# S107S1A.net
KiCad netlist of a schematic drawn in EAGLE
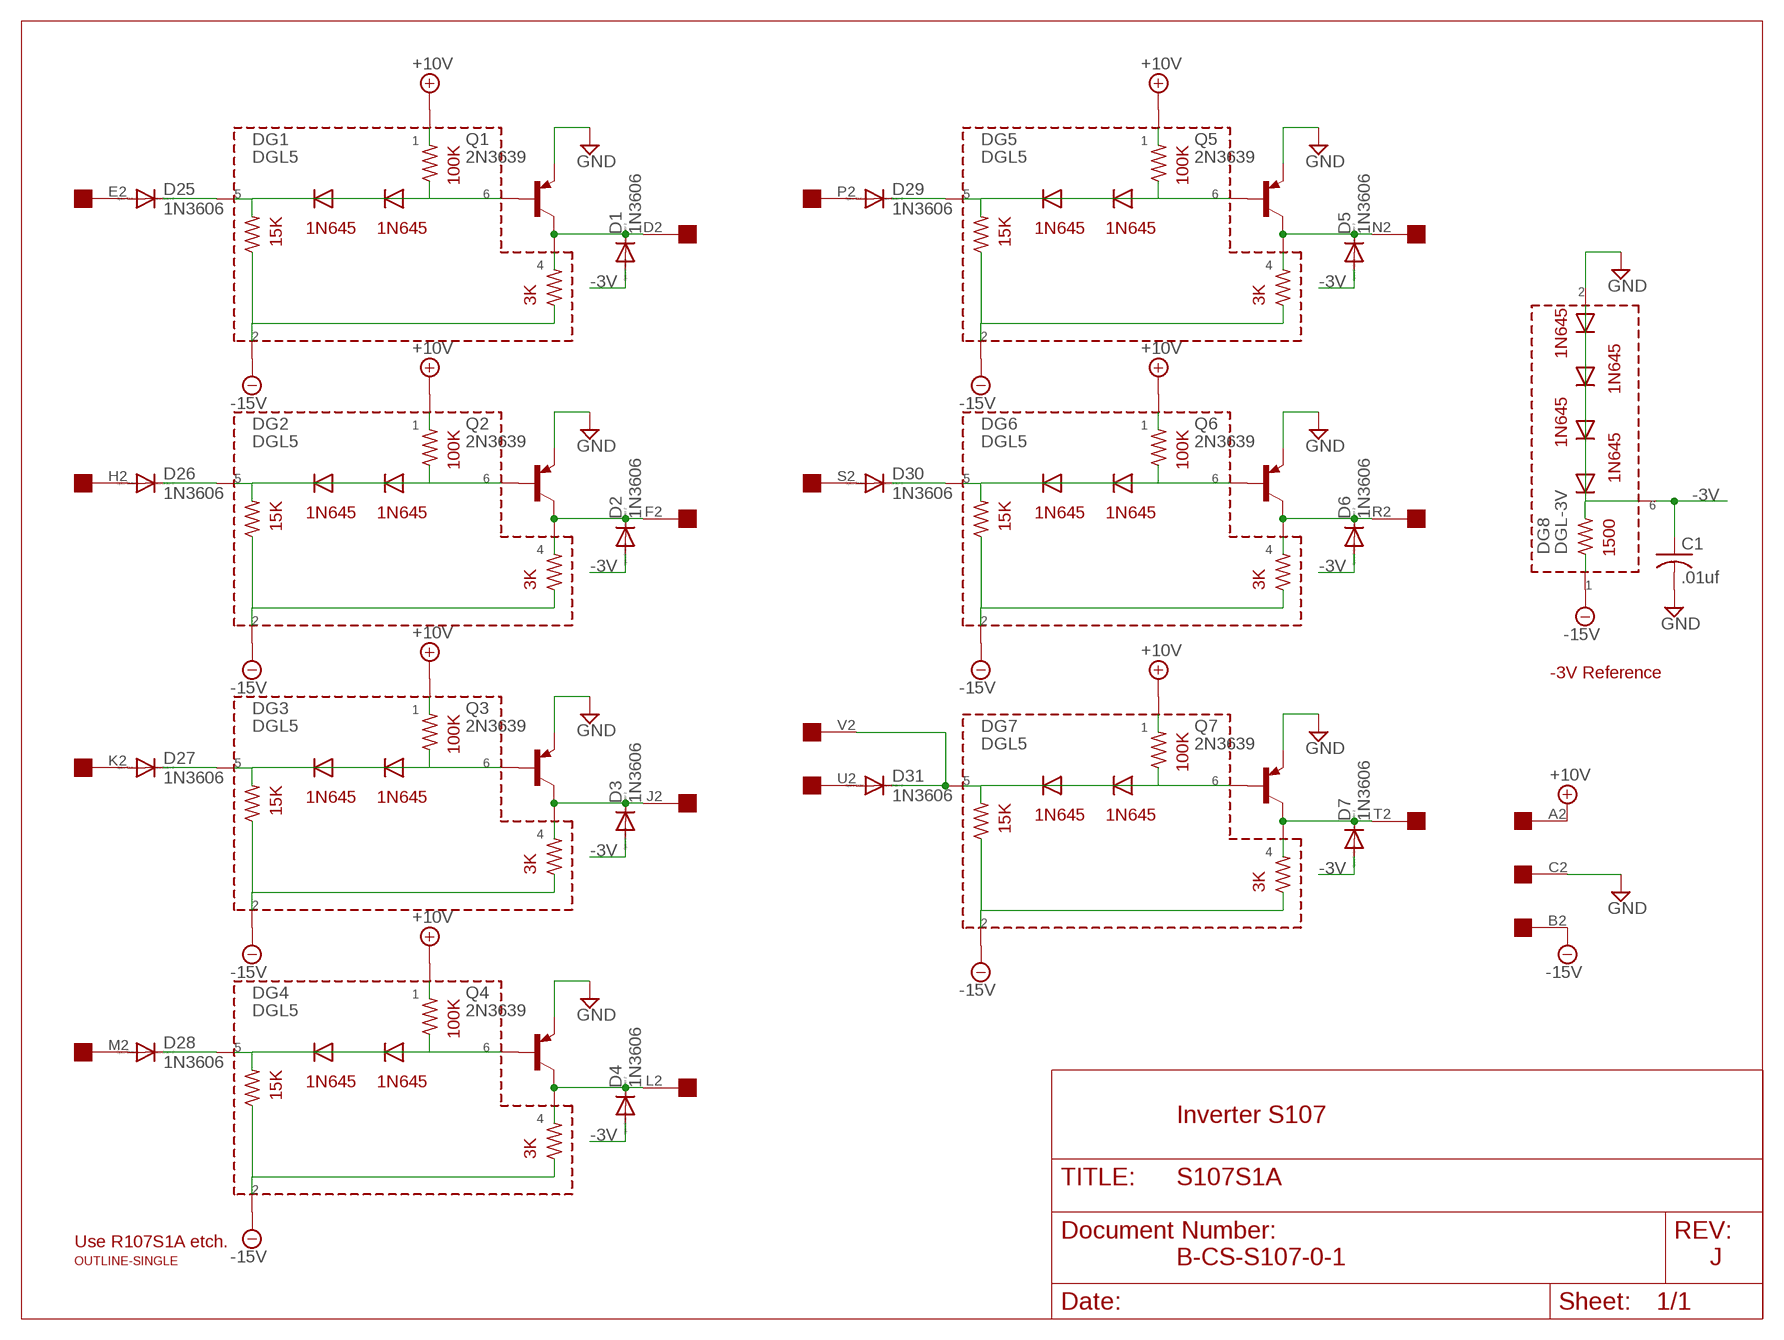
[diagram p0: schematic, sheet 1]

(export (version "E")
  (design (tool "Eeschema 10.0.6"))
  (components
    (comp (ref "C1")
      (value ".01uf")
      (footprint "eagle-import:C050-025X075")
      (libsource (lib "eagle-import") (part "C-US050-025X075"))
    )
    (comp (ref "D1")
      (value "1N3606")
      (footprint "eagle-import:DO35-10")
      (libsource (lib "eagle-import") (part "1N4148DO35-10"))
    )
    (comp (ref "D2")
      (value "1N3606")
      (footprint "eagle-import:DO35-10")
      (libsource (lib "eagle-import") (part "1N4148DO35-10"))
    )
    (comp (ref "D3")
      (value "1N3606")
      (footprint "eagle-import:DO35-10")
      (libsource (lib "eagle-import") (part "1N4148DO35-10"))
    )
    (comp (ref "D4")
      (value "1N3606")
      (footprint "eagle-import:DO35-10")
      (libsource (lib "eagle-import") (part "1N4148DO35-10"))
    )
    (comp (ref "D5")
      (value "1N3606")
      (footprint "eagle-import:DO35-10")
      (libsource (lib "eagle-import") (part "1N4148DO35-10"))
    )
    (comp (ref "D6")
      (value "1N3606")
      (footprint "eagle-import:DO35-10")
      (libsource (lib "eagle-import") (part "1N4148DO35-10"))
    )
    (comp (ref "D7")
      (value "1N3606")
      (footprint "eagle-import:DO35-10")
      (libsource (lib "eagle-import") (part "1N4148DO35-10"))
    )
    (comp (ref "D25")
      (value "1N3606")
      (footprint "eagle-import:DO35-10")
      (libsource (lib "eagle-import") (part "1N4148DO35-10"))
    )
    (comp (ref "D26")
      (value "1N3606")
      (footprint "eagle-import:DO35-10")
      (libsource (lib "eagle-import") (part "1N4148DO35-10"))
    )
    (comp (ref "D27")
      (value "1N3606")
      (footprint "eagle-import:DO35-10")
      (libsource (lib "eagle-import") (part "1N4148DO35-10"))
    )
    (comp (ref "D28")
      (value "1N3606")
      (footprint "eagle-import:DO35-10")
      (libsource (lib "eagle-import") (part "1N4148DO35-10"))
    )
    (comp (ref "D29")
      (value "1N3606")
      (footprint "eagle-import:DO35-10")
      (libsource (lib "eagle-import") (part "1N4148DO35-10"))
    )
    (comp (ref "D30")
      (value "1N3606")
      (footprint "eagle-import:DO35-10")
      (libsource (lib "eagle-import") (part "1N4148DO35-10"))
    )
    (comp (ref "D31")
      (value "1N3606")
      (footprint "eagle-import:DO35-10")
      (libsource (lib "eagle-import") (part "1N4148DO35-10"))
    )
    (comp (ref "DG1")
      (value "DGL5")
      (footprint "eagle-import:DGL2")
      (libsource (lib "eagle-import") (part "DGL5"))
    )
    (comp (ref "DG2")
      (value "DGL5")
      (footprint "eagle-import:DGL2")
      (libsource (lib "eagle-import") (part "DGL5"))
    )
    (comp (ref "DG3")
      (value "DGL5")
      (footprint "eagle-import:DGL2")
      (libsource (lib "eagle-import") (part "DGL5"))
    )
    (comp (ref "DG4")
      (value "DGL5")
      (footprint "eagle-import:DGL2")
      (libsource (lib "eagle-import") (part "DGL5"))
    )
    (comp (ref "DG5")
      (value "DGL5")
      (footprint "eagle-import:DGL2")
      (libsource (lib "eagle-import") (part "DGL5"))
    )
    (comp (ref "DG6")
      (value "DGL5")
      (footprint "eagle-import:DGL2")
      (libsource (lib "eagle-import") (part "DGL5"))
    )
    (comp (ref "DG7")
      (value "DGL5")
      (footprint "eagle-import:DGL2")
      (libsource (lib "eagle-import") (part "DGL5"))
    )
    (comp (ref "DG8")
      (value "DGL-3V")
      (footprint "eagle-import:DGL2")
      (libsource (lib "eagle-import") (part "DGL-3V"))
    )
    (comp (ref "Q1")
      (value "2N3639")
      (footprint "eagle-import:TO39")
      (libsource (lib "eagle-import") (part "2N3637"))
    )
    (comp (ref "Q2")
      (value "2N3639")
      (footprint "eagle-import:TO39")
      (libsource (lib "eagle-import") (part "2N3637"))
    )
    (comp (ref "Q3")
      (value "2N3639")
      (footprint "eagle-import:TO39")
      (libsource (lib "eagle-import") (part "2N3637"))
    )
    (comp (ref "Q4")
      (value "2N3639")
      (footprint "eagle-import:TO39")
      (libsource (lib "eagle-import") (part "2N3637"))
    )
    (comp (ref "Q5")
      (value "2N3639")
      (footprint "eagle-import:TO39")
      (libsource (lib "eagle-import") (part "2N3637"))
    )
    (comp (ref "Q6")
      (value "2N3639")
      (footprint "eagle-import:TO39")
      (libsource (lib "eagle-import") (part "2N3637"))
    )
    (comp (ref "Q7")
      (value "2N3639")
      (footprint "eagle-import:TO39")
      (libsource (lib "eagle-import") (part "2N3637"))
    )
    (comp (ref "U$1")
      (value "OUTLINE-SINGLE")
      (footprint "eagle-import:SINGLE")
      (libsource (lib "eagle-import") (part "OUTLINE-SINGLE"))
    )
    (comp (ref "U$2")
      (value "EDGE-1")
      (footprint "eagle-import:EDGE-CON1")
      (libsource (lib "eagle-import") (part "EDGE-1"))
    )
  )
  (nets
    (net (code "1") (name "+10V") (class "Default")
      (node (ref "DG1") (pin "P$1") (pinfunction "1_P$1") (pintype "passive"))
      (node (ref "DG2") (pin "P$1") (pinfunction "1_P$1") (pintype "passive"))
      (node (ref "DG3") (pin "P$1") (pinfunction "1_P$1") (pintype "passive"))
      (node (ref "DG4") (pin "P$1") (pinfunction "1_P$1") (pintype "passive"))
      (node (ref "DG5") (pin "P$1") (pinfunction "1_P$1") (pintype "passive"))
      (node (ref "DG6") (pin "P$1") (pinfunction "1_P$1") (pintype "passive"))
      (node (ref "DG7") (pin "P$1") (pinfunction "1_P$1") (pintype "passive"))
      (node (ref "U$2") (pin "A2") (pinfunction "1_A2") (pintype "bidirectional"))
    )
    (net (code "2") (name "-15V") (class "Default")
      (node (ref "DG1") (pin "P$2") (pinfunction "2_P$2") (pintype "passive"))
      (node (ref "DG2") (pin "P$2") (pinfunction "2_P$2") (pintype "passive"))
      (node (ref "DG3") (pin "P$2") (pinfunction "2_P$2") (pintype "passive"))
      (node (ref "DG4") (pin "P$2") (pinfunction "2_P$2") (pintype "passive"))
      (node (ref "DG5") (pin "P$2") (pinfunction "2_P$2") (pintype "passive"))
      (node (ref "DG6") (pin "P$2") (pinfunction "2_P$2") (pintype "passive"))
      (node (ref "DG7") (pin "P$2") (pinfunction "2_P$2") (pintype "passive"))
      (node (ref "DG8") (pin "P$1") (pinfunction "1_P$1") (pintype "passive"))
      (node (ref "U$2") (pin "B2") (pinfunction "1_B2") (pintype "bidirectional"))
    )
    (net (code "3") (name "/-3V") (class "Default")
      (node (ref "C1") (pin "1") (pinfunction "1_1") (pintype "passive"))
      (node (ref "D1") (pin "A") (pinfunction "A_A") (pintype "passive"))
      (node (ref "D2") (pin "A") (pinfunction "A_A") (pintype "passive"))
      (node (ref "D3") (pin "A") (pinfunction "A_A") (pintype "passive"))
      (node (ref "D4") (pin "A") (pinfunction "A_A") (pintype "passive"))
      (node (ref "D5") (pin "A") (pinfunction "A_A") (pintype "passive"))
      (node (ref "D6") (pin "A") (pinfunction "A_A") (pintype "passive"))
      (node (ref "D7") (pin "A") (pinfunction "A_A") (pintype "passive"))
      (node (ref "DG8") (pin "P$6") (pinfunction "6_P$6") (pintype "passive"))
    )
    (net (code "4") (name "GND") (class "Default")
      (node (ref "C1") (pin "2") (pinfunction "2_2") (pintype "passive"))
      (node (ref "DG8") (pin "P$2") (pinfunction "2_P$2") (pintype "passive"))
      (node (ref "Q1") (pin "1") (pinfunction "E_1") (pintype "passive"))
      (node (ref "Q2") (pin "1") (pinfunction "E_1") (pintype "passive"))
      (node (ref "Q3") (pin "1") (pinfunction "E_1") (pintype "passive"))
      (node (ref "Q4") (pin "1") (pinfunction "E_1") (pintype "passive"))
      (node (ref "Q5") (pin "1") (pinfunction "E_1") (pintype "passive"))
      (node (ref "Q6") (pin "1") (pinfunction "E_1") (pintype "passive"))
      (node (ref "Q7") (pin "1") (pinfunction "E_1") (pintype "passive"))
      (node (ref "U$2") (pin "C2") (pinfunction "1_C2") (pintype "bidirectional"))
    )
    (net (code "5") (name "Net-(DG1-4)") (class "Default")
      (node (ref "D1") (pin "C") (pinfunction "C_C") (pintype "passive"))
      (node (ref "DG1") (pin "P$4") (pinfunction "4_P$4") (pintype "passive"))
      (node (ref "Q1") (pin "3") (pinfunction "C_3") (pintype "passive"))
      (node (ref "U$2") (pin "D2") (pinfunction "1_D2") (pintype "bidirectional"))
    )
    (net (code "6") (name "Net-(DG1-5)") (class "Default")
      (node (ref "D25") (pin "C") (pinfunction "C_C") (pintype "passive"))
      (node (ref "DG1") (pin "P$5") (pinfunction "5_P$5") (pintype "passive"))
    )
    (net (code "7") (name "Net-(DG1-6)") (class "Default")
      (node (ref "DG1") (pin "P$6") (pinfunction "6_P$6") (pintype "passive"))
      (node (ref "Q1") (pin "2") (pinfunction "B_2") (pintype "passive"))
    )
    (net (code "8") (name "Net-(DG2-4)") (class "Default")
      (node (ref "D2") (pin "C") (pinfunction "C_C") (pintype "passive"))
      (node (ref "DG2") (pin "P$4") (pinfunction "4_P$4") (pintype "passive"))
      (node (ref "Q2") (pin "3") (pinfunction "C_3") (pintype "passive"))
      (node (ref "U$2") (pin "F2") (pinfunction "1_F2") (pintype "bidirectional"))
    )
    (net (code "9") (name "Net-(DG2-5)") (class "Default")
      (node (ref "D26") (pin "C") (pinfunction "C_C") (pintype "passive"))
      (node (ref "DG2") (pin "P$5") (pinfunction "5_P$5") (pintype "passive"))
    )
    (net (code "10") (name "Net-(DG2-6)") (class "Default")
      (node (ref "DG2") (pin "P$6") (pinfunction "6_P$6") (pintype "passive"))
      (node (ref "Q2") (pin "2") (pinfunction "B_2") (pintype "passive"))
    )
    (net (code "11") (name "Net-(DG3-4)") (class "Default")
      (node (ref "D3") (pin "C") (pinfunction "C_C") (pintype "passive"))
      (node (ref "DG3") (pin "P$4") (pinfunction "4_P$4") (pintype "passive"))
      (node (ref "Q3") (pin "3") (pinfunction "C_3") (pintype "passive"))
      (node (ref "U$2") (pin "J2") (pinfunction "1_J2") (pintype "bidirectional"))
    )
    (net (code "12") (name "Net-(DG3-5)") (class "Default")
      (node (ref "D27") (pin "C") (pinfunction "C_C") (pintype "passive"))
      (node (ref "DG3") (pin "P$5") (pinfunction "5_P$5") (pintype "passive"))
    )
    (net (code "13") (name "Net-(DG3-6)") (class "Default")
      (node (ref "DG3") (pin "P$6") (pinfunction "6_P$6") (pintype "passive"))
      (node (ref "Q3") (pin "2") (pinfunction "B_2") (pintype "passive"))
    )
    (net (code "14") (name "Net-(DG4-4)") (class "Default")
      (node (ref "D4") (pin "C") (pinfunction "C_C") (pintype "passive"))
      (node (ref "DG4") (pin "P$4") (pinfunction "4_P$4") (pintype "passive"))
      (node (ref "Q4") (pin "3") (pinfunction "C_3") (pintype "passive"))
      (node (ref "U$2") (pin "L2") (pinfunction "1_L2") (pintype "bidirectional"))
    )
    (net (code "15") (name "Net-(DG4-5)") (class "Default")
      (node (ref "D28") (pin "C") (pinfunction "C_C") (pintype "passive"))
      (node (ref "DG4") (pin "P$5") (pinfunction "5_P$5") (pintype "passive"))
    )
    (net (code "16") (name "Net-(DG4-6)") (class "Default")
      (node (ref "DG4") (pin "P$6") (pinfunction "6_P$6") (pintype "passive"))
      (node (ref "Q4") (pin "2") (pinfunction "B_2") (pintype "passive"))
    )
    (net (code "17") (name "Net-(DG5-4)") (class "Default")
      (node (ref "D5") (pin "C") (pinfunction "C_C") (pintype "passive"))
      (node (ref "DG5") (pin "P$4") (pinfunction "4_P$4") (pintype "passive"))
      (node (ref "Q5") (pin "3") (pinfunction "C_3") (pintype "passive"))
      (node (ref "U$2") (pin "N2") (pinfunction "1_N2") (pintype "bidirectional"))
    )
    (net (code "18") (name "Net-(DG5-5)") (class "Default")
      (node (ref "D29") (pin "C") (pinfunction "C_C") (pintype "passive"))
      (node (ref "DG5") (pin "P$5") (pinfunction "5_P$5") (pintype "passive"))
    )
    (net (code "19") (name "Net-(DG5-6)") (class "Default")
      (node (ref "DG5") (pin "P$6") (pinfunction "6_P$6") (pintype "passive"))
      (node (ref "Q5") (pin "2") (pinfunction "B_2") (pintype "passive"))
    )
    (net (code "20") (name "Net-(DG6-4)") (class "Default")
      (node (ref "D6") (pin "C") (pinfunction "C_C") (pintype "passive"))
      (node (ref "DG6") (pin "P$4") (pinfunction "4_P$4") (pintype "passive"))
      (node (ref "Q6") (pin "3") (pinfunction "C_3") (pintype "passive"))
      (node (ref "U$2") (pin "R2") (pinfunction "1_R2") (pintype "bidirectional"))
    )
    (net (code "21") (name "Net-(DG6-5)") (class "Default")
      (node (ref "D30") (pin "C") (pinfunction "C_C") (pintype "passive"))
      (node (ref "DG6") (pin "P$5") (pinfunction "5_P$5") (pintype "passive"))
    )
    (net (code "22") (name "Net-(DG6-6)") (class "Default")
      (node (ref "DG6") (pin "P$6") (pinfunction "6_P$6") (pintype "passive"))
      (node (ref "Q6") (pin "2") (pinfunction "B_2") (pintype "passive"))
    )
    (net (code "23") (name "Net-(DG7-4)") (class "Default")
      (node (ref "D7") (pin "C") (pinfunction "C_C") (pintype "passive"))
      (node (ref "DG7") (pin "P$4") (pinfunction "4_P$4") (pintype "passive"))
      (node (ref "Q7") (pin "3") (pinfunction "C_3") (pintype "passive"))
      (node (ref "U$2") (pin "T2") (pinfunction "1_T2") (pintype "bidirectional"))
    )
    (net (code "24") (name "Net-(DG7-5)") (class "Default")
      (node (ref "D31") (pin "C") (pinfunction "C_C") (pintype "passive"))
      (node (ref "DG7") (pin "P$5") (pinfunction "5_P$5") (pintype "passive"))
      (node (ref "U$2") (pin "V2") (pinfunction "1_V2") (pintype "bidirectional"))
    )
    (net (code "25") (name "Net-(DG7-6)") (class "Default")
      (node (ref "DG7") (pin "P$6") (pinfunction "6_P$6") (pintype "passive"))
      (node (ref "Q7") (pin "2") (pinfunction "B_2") (pintype "passive"))
    )
    (net (code "26") (name "Net-(U$2E-1)") (class "Default")
      (node (ref "D25") (pin "A") (pinfunction "A_A") (pintype "passive"))
      (node (ref "U$2") (pin "E2") (pinfunction "1_E2") (pintype "bidirectional"))
    )
    (net (code "27") (name "Net-(U$2G-1)") (class "Default")
      (node (ref "D26") (pin "A") (pinfunction "A_A") (pintype "passive"))
      (node (ref "U$2") (pin "H2") (pinfunction "1_H2") (pintype "bidirectional"))
    )
    (net (code "28") (name "Net-(U$2I-1)") (class "Default")
      (node (ref "D27") (pin "A") (pinfunction "A_A") (pintype "passive"))
      (node (ref "U$2") (pin "K2") (pinfunction "1_K2") (pintype "bidirectional"))
    )
    (net (code "29") (name "Net-(U$2K-1)") (class "Default")
      (node (ref "D28") (pin "A") (pinfunction "A_A") (pintype "passive"))
      (node (ref "U$2") (pin "M2") (pinfunction "1_M2") (pintype "bidirectional"))
    )
    (net (code "30") (name "Net-(U$2M-1)") (class "Default")
      (node (ref "D29") (pin "A") (pinfunction "A_A") (pintype "passive"))
      (node (ref "U$2") (pin "P2") (pinfunction "1_P2") (pintype "bidirectional"))
    )
    (net (code "31") (name "Net-(U$2O-1)") (class "Default")
      (node (ref "D30") (pin "A") (pinfunction "A_A") (pintype "passive"))
      (node (ref "U$2") (pin "S2") (pinfunction "1_S2") (pintype "bidirectional"))
    )
    (net (code "32") (name "Net-(U$2Q-1)") (class "Default")
      (node (ref "D31") (pin "A") (pinfunction "A_A") (pintype "passive"))
      (node (ref "U$2") (pin "U2") (pinfunction "1_U2") (pintype "bidirectional"))
    )
  )
)
